# fv-1.net
KiCad netlist of a schematic drawn in EAGLE
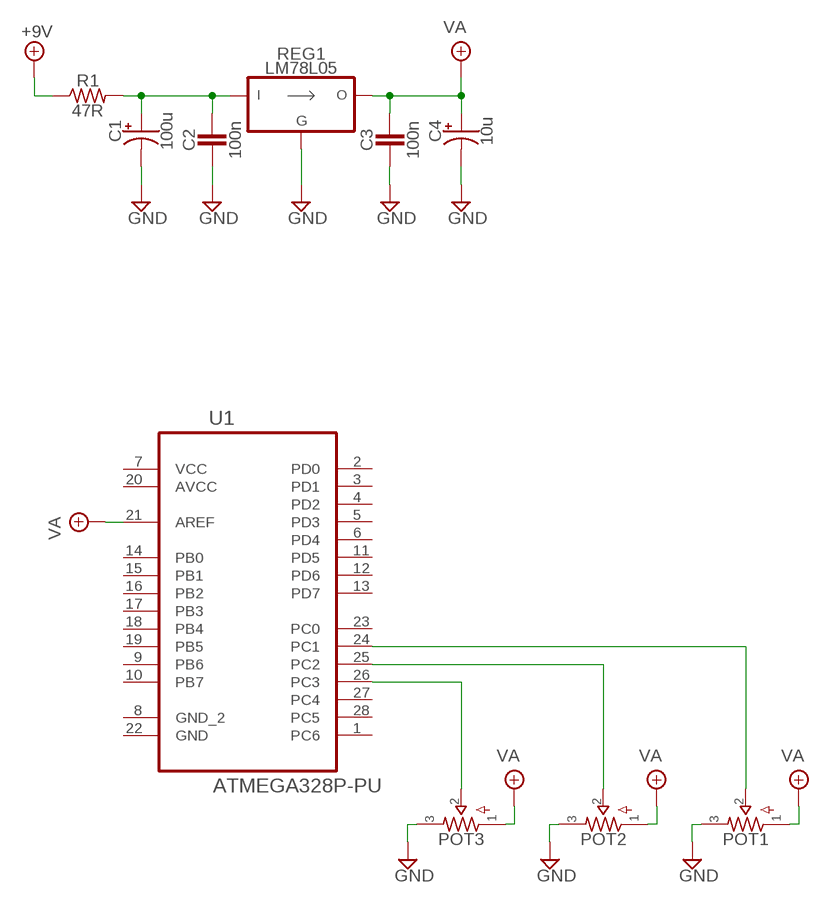
[diagram p0: schematic, sheet 1]

(export (version "E")
  (design (tool "Eeschema 10.0.6"))
  (components
    (comp (ref "C1")
      (value "100u")
      (footprint "eagle-import:050_020_1")
      (libsource (lib "eagle-import") (part "0501"))
    )
    (comp (ref "C2")
      (value "100n")
      (footprint "eagle-import:050X030_025_2")
      (libsource (lib "eagle-import") (part "CER/FILM2"))
    )
    (comp (ref "C3")
      (value "100n")
      (footprint "eagle-import:050X030_025_2")
      (libsource (lib "eagle-import") (part "CER/FILM2"))
    )
    (comp (ref "C4")
      (value "10u")
      (footprint "eagle-import:050_020_1")
      (libsource (lib "eagle-import") (part "0501"))
    )
    (comp (ref "POT1")
      (value "POTS16MM")
      (footprint "eagle-import:16MM")
      (libsource (lib "eagle-import") (part "POTS16MM"))
    )
    (comp (ref "POT2")
      (value "POTS16MM")
      (footprint "eagle-import:16MM")
      (libsource (lib "eagle-import") (part "POTS16MM"))
    )
    (comp (ref "POT3")
      (value "POTS16MM")
      (footprint "eagle-import:16MM")
      (libsource (lib "eagle-import") (part "POTS16MM"))
    )
    (comp (ref "R1")
      (value "47R")
      (footprint "eagle-import:R0207_3")
      (libsource (lib "eagle-import") (part "R_.3B"))
    )
    (comp (ref "REG1")
      (value "LM78L05")
      (footprint "eagle-import:TO92-")
      (libsource (lib "eagle-import") (part "LM78L05"))
    )
    (comp (ref "U1")
      (value "ATMEGA328P-PU")
      (footprint "eagle-import:DIP254P762X457-28")
      (libsource (lib "eagle-import") (part "ATMEGA328P-PU"))
    )
  )
  (nets
    (net (code "1") (name "+9V") (class "Default")
      (node (ref "R1") (pin "1") (pinfunction "1_1") (pintype "passive"))
    )
    (net (code "2") (name "/AVCC") (class "Default")
      (node (ref "U1") (pin "20") (pinfunction "AVCC_20") (pintype "power_in"))
    )
    (net (code "3") (name "/VCC") (class "Default")
      (node (ref "U1") (pin "7") (pinfunction "VCC_7") (pintype "power_in"))
    )
    (net (code "4") (name "GND") (class "Default")
      (node (ref "C1") (pin "-") (pinfunction "-_-") (pintype "passive"))
      (node (ref "C2") (pin "2") (pinfunction "2_2") (pintype "passive"))
      (node (ref "C3") (pin "2") (pinfunction "2_2") (pintype "passive"))
      (node (ref "C4") (pin "-") (pinfunction "-_-") (pintype "passive"))
      (node (ref "POT1") (pin "3") (pinfunction "3_3") (pintype "passive"))
      (node (ref "POT2") (pin "3") (pinfunction "3_3") (pintype "passive"))
      (node (ref "POT3") (pin "3") (pinfunction "3_3") (pintype "passive"))
      (node (ref "REG1") (pin "2") (pinfunction "GND_2") (pintype "passive"))
    )
    (net (code "5") (name "Net-(REG1-VI)") (class "Default")
      (node (ref "C1") (pin "+") (pinfunction "+_+") (pintype "passive"))
      (node (ref "C2") (pin "1") (pinfunction "1_1") (pintype "passive"))
      (node (ref "R1") (pin "2") (pinfunction "2_2") (pintype "passive"))
      (node (ref "REG1") (pin "1") (pinfunction "VI_1") (pintype "input"))
    )
    (net (code "6") (name "Net-(U1-PC1)") (class "Default")
      (node (ref "POT1") (pin "2") (pinfunction "2_2") (pintype "passive"))
      (node (ref "U1") (pin "24") (pinfunction "PC1_24") (pintype "bidirectional"))
    )
    (net (code "7") (name "Net-(U1-PC2)") (class "Default")
      (node (ref "POT2") (pin "2") (pinfunction "2_2") (pintype "passive"))
      (node (ref "U1") (pin "25") (pinfunction "PC2_25") (pintype "bidirectional"))
    )
    (net (code "8") (name "Net-(U1-PC3)") (class "Default")
      (node (ref "POT3") (pin "2") (pinfunction "2_2") (pintype "passive"))
      (node (ref "U1") (pin "26") (pinfunction "PC3_26") (pintype "bidirectional"))
    )
    (net (code "9") (name "VA") (class "Default")
      (node (ref "C3") (pin "1") (pinfunction "1_1") (pintype "passive"))
      (node (ref "C4") (pin "+") (pinfunction "+_+") (pintype "passive"))
      (node (ref "POT1") (pin "1") (pinfunction "1_1") (pintype "passive"))
      (node (ref "POT2") (pin "1") (pinfunction "1_1") (pintype "passive"))
      (node (ref "POT3") (pin "1") (pinfunction "1_1") (pintype "passive"))
      (node (ref "REG1") (pin "3") (pinfunction "VO_3") (pintype "passive"))
      (node (ref "U1") (pin "21") (pinfunction "AREF_21") (pintype "input"))
    )
    (net (code "10") (name "unconnected-(U1-GND-Pad22)") (class "Default")
      (node (ref "U1") (pin "22") (pinfunction "GND_22") (pintype "passive"))
    )
    (net (code "11") (name "unconnected-(U1-GND_2-Pad8)") (class "Default")
      (node (ref "U1") (pin "8") (pinfunction "GND_2_8") (pintype "passive"))
    )
    (net (code "12") (name "unconnected-(U1-PB0-Pad14)") (class "Default")
      (node (ref "U1") (pin "14") (pinfunction "PB0_14") (pintype "bidirectional"))
    )
    (net (code "13") (name "unconnected-(U1-PB1-Pad15)") (class "Default")
      (node (ref "U1") (pin "15") (pinfunction "PB1_15") (pintype "bidirectional"))
    )
    (net (code "14") (name "unconnected-(U1-PB2-Pad16)") (class "Default")
      (node (ref "U1") (pin "16") (pinfunction "PB2_16") (pintype "bidirectional"))
    )
    (net (code "15") (name "unconnected-(U1-PB3-Pad17)") (class "Default")
      (node (ref "U1") (pin "17") (pinfunction "PB3_17") (pintype "bidirectional"))
    )
    (net (code "16") (name "unconnected-(U1-PB4-Pad18)") (class "Default")
      (node (ref "U1") (pin "18") (pinfunction "PB4_18") (pintype "bidirectional"))
    )
    (net (code "17") (name "unconnected-(U1-PB5-Pad19)") (class "Default")
      (node (ref "U1") (pin "19") (pinfunction "PB5_19") (pintype "bidirectional"))
    )
    (net (code "18") (name "unconnected-(U1-PB6-Pad9)") (class "Default")
      (node (ref "U1") (pin "9") (pinfunction "PB6_9") (pintype "bidirectional"))
    )
    (net (code "19") (name "unconnected-(U1-PB7-Pad10)") (class "Default")
      (node (ref "U1") (pin "10") (pinfunction "PB7_10") (pintype "bidirectional"))
    )
    (net (code "20") (name "unconnected-(U1-PC0-Pad23)") (class "Default")
      (node (ref "U1") (pin "23") (pinfunction "PC0_23") (pintype "bidirectional"))
    )
    (net (code "21") (name "unconnected-(U1-PC4-Pad27)") (class "Default")
      (node (ref "U1") (pin "27") (pinfunction "PC4_27") (pintype "bidirectional"))
    )
    (net (code "22") (name "unconnected-(U1-PC5-Pad28)") (class "Default")
      (node (ref "U1") (pin "28") (pinfunction "PC5_28") (pintype "bidirectional"))
    )
    (net (code "23") (name "unconnected-(U1-PC6-Pad1)") (class "Default")
      (node (ref "U1") (pin "1") (pinfunction "PC6_1") (pintype "bidirectional"))
    )
    (net (code "24") (name "unconnected-(U1-PD0-Pad2)") (class "Default")
      (node (ref "U1") (pin "2") (pinfunction "PD0_2") (pintype "bidirectional"))
    )
    (net (code "25") (name "unconnected-(U1-PD1-Pad3)") (class "Default")
      (node (ref "U1") (pin "3") (pinfunction "PD1_3") (pintype "bidirectional"))
    )
    (net (code "26") (name "unconnected-(U1-PD2-Pad4)") (class "Default")
      (node (ref "U1") (pin "4") (pinfunction "PD2_4") (pintype "bidirectional"))
    )
    (net (code "27") (name "unconnected-(U1-PD3-Pad5)") (class "Default")
      (node (ref "U1") (pin "5") (pinfunction "PD3_5") (pintype "bidirectional"))
    )
    (net (code "28") (name "unconnected-(U1-PD4-Pad6)") (class "Default")
      (node (ref "U1") (pin "6") (pinfunction "PD4_6") (pintype "bidirectional"))
    )
    (net (code "29") (name "unconnected-(U1-PD5-Pad11)") (class "Default")
      (node (ref "U1") (pin "11") (pinfunction "PD5_11") (pintype "bidirectional"))
    )
    (net (code "30") (name "unconnected-(U1-PD6-Pad12)") (class "Default")
      (node (ref "U1") (pin "12") (pinfunction "PD6_12") (pintype "bidirectional"))
    )
    (net (code "31") (name "unconnected-(U1-PD7-Pad13)") (class "Default")
      (node (ref "U1") (pin "13") (pinfunction "PD7_13") (pintype "bidirectional"))
    )
  )
)
